# Sheet1_Pt100.net
KiCad netlist of a schematic drawn in Altium Designer
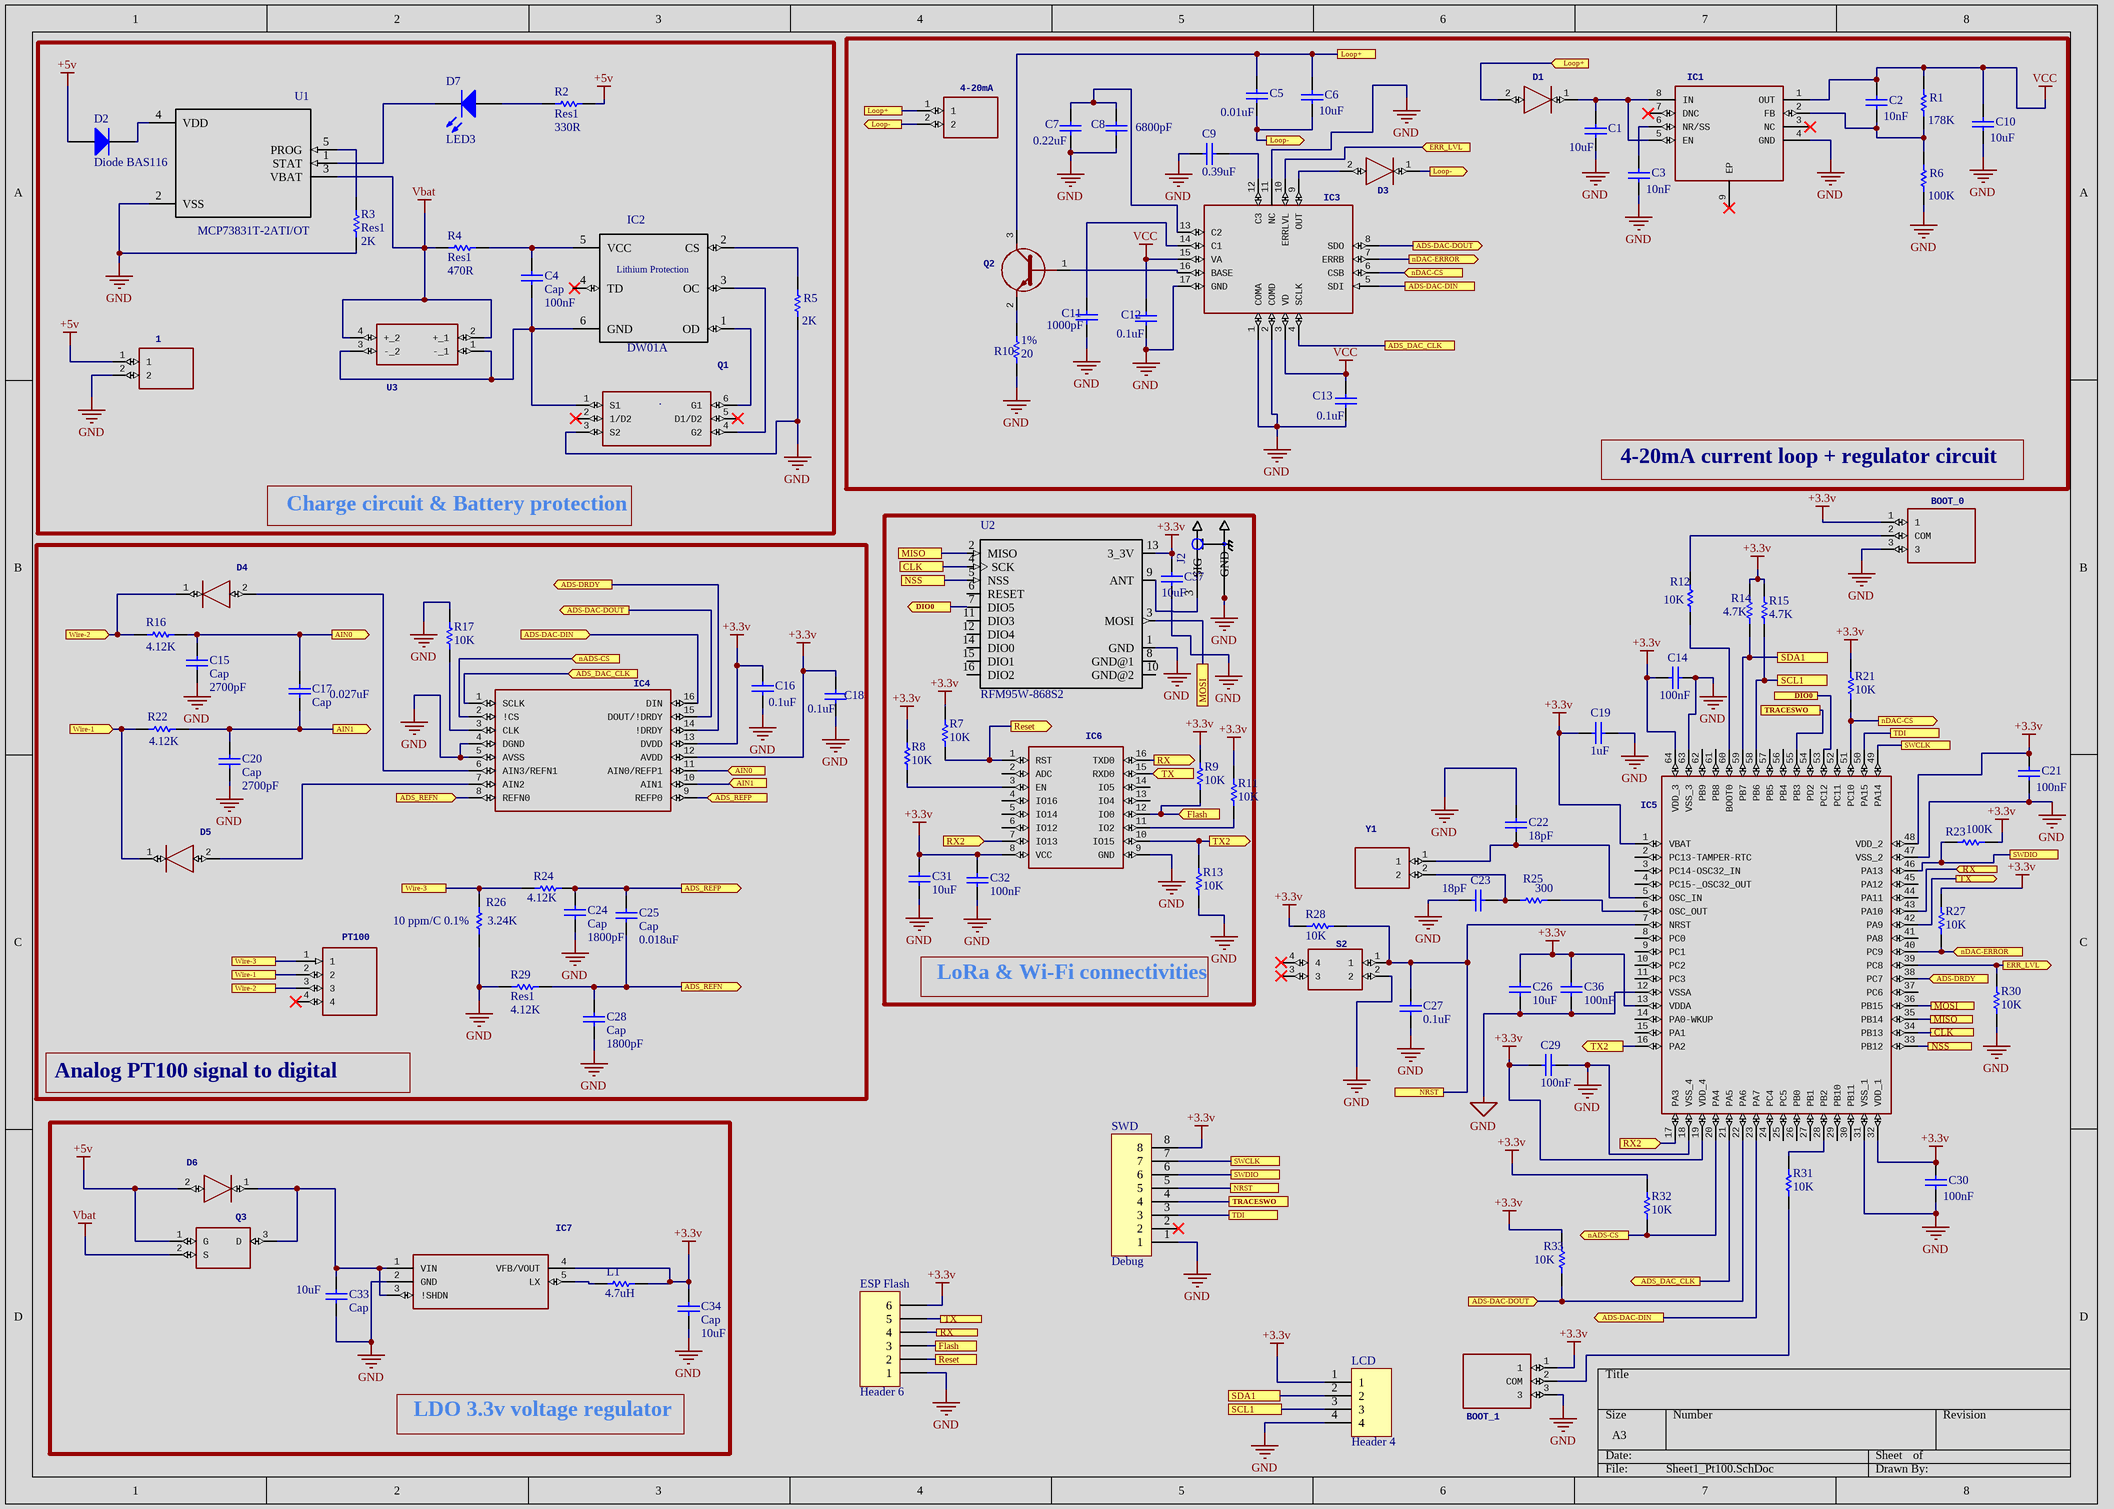
[diagram p0: Sheet1_Pt100.SchDoc]

(export (version "E")
  (design (tool "Eeschema 10.0.6"))
  (components
    (comp (ref "1")
      (value "P=3.81mm Screw terminal   Source:  Datasheet")
      (footprint "SHDR2W80P0X381_1X2_802X740X880")
      (fields (field (name "MANUFACTURER_PART_NUMBER") "DB125-3.81-2P"))
      (libsource (lib "DB125-3") (part "DB125-3.81-2P"))
    )
    (comp (ref "4-20mA")
      (value "P=3.81mm Screw terminal   Source:  Datasheet")
      (footprint "SHDR2W80P0X381_1X2_802X740X880")
      (fields (field (name "MANUFACTURER_PART_NUMBER") "DB125-3.81-2P"))
      (libsource (lib "DB125-3") (part "DB125-3.81-2P"))
    )
    (comp (ref "BOOT_0")
      (value "Slide Switch   Source:  Datasheet")
      (footprint "3PIN_SLIDE_SWITCH")
      (fields
        (field (name "MANUFACTURER_PART_NUMBER") "EG1218")
        (field (name "MOUSER_PART_NUMBER") "612-EG1218")
      )
      (libsource (lib "EG1218") (part "EG1218"))
    )
    (comp (ref "BOOT_1")
      (value "Slide Switch   Source:  Datasheet")
      (footprint "3PIN_SLIDE_SWITCH")
      (fields
        (field (name "MANUFACTURER_PART_NUMBER") "EG1218")
        (field (name "MOUSER_PART_NUMBER") "612-EG1218")
      )
      (libsource (lib "EG1218") (part "EG1218"))
    )
    (comp (ref "C1")
      (value "10uF")
      (footprint "C1206")
      (description "Capacitor")
      (fields (field (name "PUBLISHER") "Altium Limited"))
      (libsource (lib "Miscellaneous Devices") (part "Cap"))
    )
    (comp (ref "C2")
      (value "10nF")
      (footprint "C1206")
      (description "Capacitor")
      (fields (field (name "PUBLISHER") "Altium Limited"))
      (libsource (lib "Miscellaneous Devices") (part "Cap"))
    )
    (comp (ref "C3")
      (value "10nF")
      (footprint "C1206")
      (description "Capacitor")
      (fields (field (name "PUBLISHER") "Altium Limited"))
      (libsource (lib "Miscellaneous Devices") (part "Cap"))
    )
    (comp (ref "C4")
      (value "Cap")
      (footprint "C1206")
      (description "Capacitor")
      (fields (field (name "ALTIUM_VALUE") "100nF") (field (name "PUBLISHER") "Altium Limited"))
      (libsource (lib "Miscellaneous Devices") (part "Cap"))
    )
    (comp (ref "C5")
      (value "0.01uF")
      (footprint "C1206")
      (description "Capacitor")
      (fields (field (name "PUBLISHER") "Altium Limited"))
      (libsource (lib "Miscellaneous Devices") (part "Cap"))
    )
    (comp (ref "C6")
      (value "10uF")
      (footprint "C1206")
      (description "Capacitor")
      (fields (field (name "PUBLISHER") "Altium Limited"))
      (libsource (lib "Miscellaneous Devices") (part "Cap"))
    )
    (comp (ref "C7")
      (value "0.22uF")
      (footprint "C1206")
      (description "Capacitor")
      (fields (field (name "PUBLISHER") "Altium Limited"))
      (libsource (lib "Miscellaneous Devices") (part "Cap"))
    )
    (comp (ref "C8")
      (value "6800pF")
      (footprint "C1206")
      (description "Capacitor")
      (fields (field (name "PUBLISHER") "Altium Limited"))
      (libsource (lib "Miscellaneous Devices") (part "Cap"))
    )
    (comp (ref "C9")
      (value "0.39uF")
      (footprint "C1206")
      (description "Capacitor")
      (fields (field (name "PUBLISHER") "Altium Limited"))
      (libsource (lib "Miscellaneous Devices") (part "Cap"))
    )
    (comp (ref "C10")
      (value "10uF")
      (footprint "C1206")
      (description "Capacitor")
      (fields (field (name "PUBLISHER") "Altium Limited"))
      (libsource (lib "Miscellaneous Devices") (part "Cap"))
    )
    (comp (ref "C11")
      (value "1000pF")
      (footprint "C1206")
      (description "Capacitor")
      (fields (field (name "PUBLISHER") "Altium Limited"))
      (libsource (lib "Miscellaneous Devices") (part "Cap"))
    )
    (comp (ref "C12")
      (value "0.1uF")
      (footprint "C1206")
      (description "Capacitor")
      (fields (field (name "PUBLISHER") "Altium Limited"))
      (libsource (lib "Miscellaneous Devices") (part "Cap"))
    )
    (comp (ref "C13")
      (value "0.1uF")
      (footprint "C1206")
      (description "Capacitor")
      (fields (field (name "PUBLISHER") "Altium Limited"))
      (libsource (lib "Miscellaneous Devices") (part "Cap"))
    )
    (comp (ref "C14")
      (value "100nF")
      (footprint "C1206")
      (description "Capacitor")
      (fields (field (name "PUBLISHER") "Altium Limited"))
      (libsource (lib "Miscellaneous Devices") (part "Cap"))
    )
    (comp (ref "C15")
      (value "Cap")
      (footprint "C1206")
      (description "Capacitor")
      (fields (field (name "ALTIUM_VALUE") "2700pF") (field (name "PUBLISHER") "Altium Limited"))
      (libsource (lib "Miscellaneous Devices") (part "Cap"))
    )
    (comp (ref "C16")
      (value "0.1uF")
      (footprint "C1206")
      (description "Capacitor")
      (fields (field (name "PUBLISHER") "Altium Limited"))
      (libsource (lib "Miscellaneous Devices") (part "Cap"))
    )
    (comp (ref "C17")
      (value "Cap")
      (footprint "C1206")
      (description "Capacitor")
      (fields (field (name "ALTIUM_VALUE") "0.027uF") (field (name "PUBLISHER") "Altium Limited"))
      (libsource (lib "Miscellaneous Devices") (part "Cap"))
    )
    (comp (ref "C18")
      (value "0.1uF")
      (footprint "C1206")
      (description "Capacitor")
      (fields (field (name "PUBLISHER") "Altium Limited"))
      (libsource (lib "Miscellaneous Devices") (part "Cap"))
    )
    (comp (ref "C19")
      (value "1uF")
      (footprint "C1206")
      (description "Capacitor")
      (fields (field (name "PUBLISHER") "Altium Limited"))
      (libsource (lib "Miscellaneous Devices") (part "Cap"))
    )
    (comp (ref "C20")
      (value "Cap")
      (footprint "C1206")
      (description "Capacitor")
      (fields (field (name "ALTIUM_VALUE") "2700pF") (field (name "PUBLISHER") "Altium Limited"))
      (libsource (lib "Miscellaneous Devices") (part "Cap"))
    )
    (comp (ref "C21")
      (value "100nF")
      (footprint "C1206")
      (description "Capacitor")
      (fields (field (name "PUBLISHER") "Altium Limited"))
      (libsource (lib "Miscellaneous Devices") (part "Cap"))
    )
    (comp (ref "C22")
      (value "18pF")
      (footprint "C1206")
      (description "Capacitor")
      (fields (field (name "PUBLISHER") "Altium Limited"))
      (libsource (lib "Miscellaneous Devices") (part "Cap"))
    )
    (comp (ref "C23")
      (value "18pF")
      (footprint "C1206")
      (description "Capacitor")
      (fields (field (name "PUBLISHER") "Altium Limited"))
      (libsource (lib "Miscellaneous Devices") (part "Cap"))
    )
    (comp (ref "C24")
      (value "Cap")
      (footprint "C1206")
      (description "Capacitor")
      (fields (field (name "ALTIUM_VALUE") "1800pF") (field (name "PUBLISHER") "Altium Limited"))
      (libsource (lib "Miscellaneous Devices") (part "Cap"))
    )
    (comp (ref "C25")
      (value "Cap")
      (footprint "C1206")
      (description "Capacitor")
      (fields (field (name "ALTIUM_VALUE") "0.018uF") (field (name "PUBLISHER") "Altium Limited"))
      (libsource (lib "Miscellaneous Devices") (part "Cap"))
    )
    (comp (ref "C26")
      (value "10uF")
      (footprint "C1206")
      (description "Capacitor")
      (fields (field (name "PUBLISHER") "Altium Limited"))
      (libsource (lib "Miscellaneous Devices") (part "Cap"))
    )
    (comp (ref "C27")
      (value "0.1uF")
      (footprint "C1206")
      (description "Capacitor")
      (fields (field (name "PUBLISHER") "Altium Limited"))
      (libsource (lib "Miscellaneous Devices") (part "Cap"))
    )
    (comp (ref "C28")
      (value "Cap")
      (footprint "C1206")
      (description "Capacitor")
      (fields (field (name "ALTIUM_VALUE") "1800pF") (field (name "PUBLISHER") "Altium Limited"))
      (libsource (lib "Miscellaneous Devices") (part "Cap"))
    )
    (comp (ref "C29")
      (value "100nF")
      (footprint "C1206")
      (description "Capacitor")
      (fields (field (name "PUBLISHER") "Altium Limited"))
      (libsource (lib "Miscellaneous Devices") (part "Cap"))
    )
    (comp (ref "C30")
      (value "100nF")
      (footprint "C1206")
      (description "Capacitor")
      (fields (field (name "PUBLISHER") "Altium Limited"))
      (libsource (lib "Miscellaneous Devices") (part "Cap"))
    )
    (comp (ref "C31")
      (value "10uF")
      (footprint "C1206")
      (description "Capacitor")
      (fields (field (name "PUBLISHER") "Altium Limited"))
      (libsource (lib "Miscellaneous Devices") (part "Cap"))
    )
    (comp (ref "C32")
      (value "100nF")
      (footprint "C1206")
      (description "Capacitor")
      (fields (field (name "PUBLISHER") "Altium Limited"))
      (libsource (lib "Miscellaneous Devices") (part "Cap"))
    )
    (comp (ref "C33")
      (value "Cap")
      (footprint "C1206")
      (description "Capacitor")
      (fields (field (name "ALTIUM_VALUE") "10uF") (field (name "PUBLISHER") "Altium Limited"))
      (libsource (lib "Miscellaneous Devices") (part "Cap"))
    )
    (comp (ref "C34")
      (value "Cap")
      (footprint "C1206")
      (description "Capacitor")
      (fields (field (name "ALTIUM_VALUE") "10uF") (field (name "PUBLISHER") "Altium Limited"))
      (libsource (lib "Miscellaneous Devices") (part "Cap"))
    )
    (comp (ref "C36")
      (value "100nF")
      (footprint "C1206")
      (description "Capacitor")
      (fields (field (name "PUBLISHER") "Altium Limited"))
      (libsource (lib "Miscellaneous Devices") (part "Cap"))
    )
    (comp (ref "C37")
      (value "10uF")
      (footprint "C1206")
      (description "Capacitor")
      (fields (field (name "PUBLISHER") "Altium Limited"))
      (libsource (lib "Miscellaneous Devices") (part "Cap"))
    )
    (comp (ref "D1")
      (value "Diodes Inc 40V 350mA, Diode, 2-Pin SOD-523 ZHCS350TA   Source:  Datasheet")
      (footprint "SODFL1608X65N")
      (fields
        (field (name "MANUFACTURER_PART_NUMBER") "ZHCS350TA")
        (field (name "MOUSER_PART_NUMBER") "522-ZHCS350TA")
        (field (name "RS_PART_NUMBER") "7515168P")
      )
      (libsource (lib "ZHCS350TA") (part "ZHCS350TA"))
    )
    (comp (ref "D2")
      (value "Diode BAS116")
      (footprint "SOT-23_N")
      (description "Silicon Low Leakage Diode")
      (fields (field (name "PUBLISHER") "Altium Limited"))
      (libsource (lib "Miscellaneous Devices") (part "Diode BAS116"))
    )
    (comp (ref "D3")
      (value "Diodes Inc 40V 350mA, Diode, 2-Pin SOD-523 ZHCS350TA   Source:  Datasheet")
      (footprint "SODFL1608X65N")
      (fields
        (field (name "MANUFACTURER_PART_NUMBER") "ZHCS350TA")
        (field (name "MOUSER_PART_NUMBER") "522-ZHCS350TA")
        (field (name "RS_PART_NUMBER") "7515168P")
      )
      (libsource (lib "ZHCS350TA") (part "ZHCS350TA"))
    )
    (comp (ref "D4")
      (value "Diodes Inc 40V 350mA, Diode, 2-Pin SOD-523 ZHCS350TA   Source:  Datasheet")
      (footprint "SODFL1608X65N")
      (fields
        (field (name "MANUFACTURER_PART_NUMBER") "ZHCS350TA")
        (field (name "MOUSER_PART_NUMBER") "522-ZHCS350TA")
        (field (name "RS_PART_NUMBER") "7515168P")
      )
      (libsource (lib "ZHCS350TA") (part "ZHCS350TA"))
    )
    (comp (ref "D5")
      (value "Diodes Inc 40V 350mA, Diode, 2-Pin SOD-523 ZHCS350TA   Source:  Datasheet")
      (footprint "SODFL1608X65N")
      (fields
        (field (name "MANUFACTURER_PART_NUMBER") "ZHCS350TA")
        (field (name "MOUSER_PART_NUMBER") "522-ZHCS350TA")
        (field (name "RS_PART_NUMBER") "7515168P")
      )
      (libsource (lib "ZHCS350TA") (part "ZHCS350TA"))
    )
    (comp (ref "D6")
      (value "Diode, NXP, PMEG3010ER NXP PMEG3010ER, SMT Schottky Diode, 30V 1A, 2-Pin SOD-123   Source:  Datasheet")
      (footprint "SODFL3517X110N")
      (fields (field (name "MANUFACTURER_PART_NUMBER") "PMEG3010ER"))
      (libsource (lib "PMEG3010ER") (part "PMEG3010ER"))
    )
    (comp (ref "D7")
      (value "LED3")
      (footprint "3.5X2.8X1.9")
      (description "Typical BLUE SiC LED")
      (fields (field (name "PUBLISHER") "Altium Limited"))
      (libsource (lib "Miscellaneous Devices") (part "LED3"))
    )
    (comp (ref "ESP Flash")
      (value "Header 6")
      (footprint "HDR1X6")
      (description "Header, 6-Pin")
      (fields (field (name "PUBLISHER") "Altium Limited"))
      (libsource (lib "Miscellaneous Connectors") (part "Header 6"))
    )
    (comp (ref "IC1")
      (value "Vin 3V to 36V, 150mA, Ultra-Low-Noise, High-PSRR Low-Dropout (LDO) Linear Regulator   Source:  Datasheet")
      (footprint "SOP65P490X110-9N")
      (fields
        (field (name "MANUFACTURER_PART_NUMBER") "TPS7A4901DGNR")
        (field (name "MOUSER_PART_NUMBER") "595-TPS7A4901DGNR")
      )
      (libsource (lib "TPS7A4901DGNR") (part "TPS7A4901DGNR"))
    )
    (comp (ref "IC2")
      (value "DW01A")
      (footprint "*SOT23-6")
      (description "One Cell Lithium-ion/Polymer Battery Protection IC")
      (fields (field (name "MF") "Fortune Semiconductor"))
      (libsource (lib "DW01A") (part "DW01A"))
    )
    (comp (ref "IC3")
      (value "16-Bit Precision DAC With Internal Reference and 4mA-to-20mA Current Loop Drive   Source:  Datasheet")
      (footprint "QFN50P400X400X80-17N")
      (fields
        (field (name "MANUFACTURER_PART_NUMBER") "DAC161S997RGHR")
        (field (name "MOUSER_PART_NUMBER") "595-DAC161S997RGHR")
      )
      (libsource (lib "DAC161S997RGHR") (part "DAC161S997RGHR"))
    )
    (comp (ref "IC4")
      (value "24-bit, 2-kSPS, 4-ch, low-power, small-size delta-sigma ADC w/ PGA, VREF, 2x IDACs & SPI interface   Source:  Datasheet")
      (footprint "SOP65P640X120-16N")
      (fields
        (field (name "MANUFACTURER_PART_NUMBER") "ADS1220IPWR")
        (field (name "MOUSER_PART_NUMBER") "595-ADS1220IPWR")
      )
      (libsource (lib "ADS1220IPWR") (part "ADS1220IPWR"))
    )
    (comp (ref "IC5")
      (value "STM32F103RBT6, 32 bit ARM Cortex M3 Microcontroller 72MHz 128kb Flash, 20kb RAM, USB I2C SPI 64-Pin LQFP   Source:  Datasheet")
      (footprint "STM32F103RBT6:*QFP50P1200X1200X160-64N")
      (fields
        (field (name "MANUFACTURER_PART_NUMBER") "STM32F103RBT6")
        (field (name "MOUSER_PART_NUMBER") "511-STM32F103RBT6")
        (field (name "RS_PART_NUMBER") "0402251P")
      )
      (libsource (lib "STM32F103RBT6") (part "STM32F103RBT6"))
    )
    (comp (ref "IC6")
      (value "RF SOLUTIONS - ESP-12S - WIFI MODULE, 2.484GHZ, 9 I/O PORT   Source:  Datasheet")
      (footprint "ESP12S")
      (fields
        (field (name "MANUFACTURER_PART_NUMBER") "ESP-12S")
        (field (name "MOUSER_PART_NUMBER") "223-ESP-12S")
        (field (name "RS_PART_NUMBER") "1697593")
      )
      (libsource (lib "ESP-12S") (part "ESP-12S"))
    )
    (comp (ref "IC7")
      (value "Sw. Reg. PWM/PFM 2MHz 500mA 3.3V TSOT5   Source:  Datasheet")
      (footprint "SOT95P280X110-5N")
      (fields
        (field (name "MANUFACTURER_PART_NUMBER") "MCP1603T-330I/OS")
        (field (name "MOUSER_PART_NUMBER") "579-MCP1603T-330I/OS")
        (field (name "RS_PART_NUMBER") "7386235P")
      )
      (libsource (lib "MCP1603T-330I_OS") (part "MCP1603T-330I_OS"))
    )
    (comp (ref "J2")
      (value "U.FL-R-SMT(01)")
      (footprint "*HRS_U.FL-R-SMT(01)")
      (description "U.FL _UMCC_ Connector Receptacle, Male Pin 50Ohm Surface Mount Solder")
      (fields (field (name "MF") "Hirose") (field (name "MP") "U.FL-R-SMT_01_"))
      (libsource (lib "U.FL-R-SMT_01_") (part "U.FL-R-SMT(01)"))
    )
    (comp (ref "L1")
      (value "4.7uH")
      (footprint "Miscellaneous Devices:C1206")
      (description "Resistor")
      (fields (field (name "PUBLISHER") "Altium Limited"))
      (libsource (lib "Miscellaneous Devices") (part "Res1"))
    )
    (comp (ref "LCD")
      (value "Header 4")
      (footprint "HDR1X4")
      (description "Header, 4-Pin")
      (fields (field (name "PUBLISHER") "Altium Limited"))
      (libsource (lib "Miscellaneous Connectors") (part "Header 4"))
    )
    (comp (ref "PT100")
      (value "European P.C.B. type terminal blocks  EK series 4 pole   Source:  Datasheet")
      (footprint "SHDR4W90P0X381_1X4_1524X740X85")
      (fields (field (name "MANUFACTURER_PART_NUMBER") "EK381V-04P"))
      (libsource (lib "EK381V-04P") (part "EK381V-04P"))
    )
    (comp (ref "Q1")
      (value "Dual N-Channel Enhancement Mode MOSFET   Source:  Datasheet")
      (footprint "UMW8205A:SOT95P285X140-6N")
      (fields (field (name "MANUFACTURER_PART_NUMBER") "UMW8205A"))
      (libsource (lib "UMW8205A") (part "UMW8205A"))
    )
    (comp (ref "Q2")
      (value "MMBT3904 - NPN switching transistor   Source:  Datasheet")
      (footprint "SOT95P230X110-3N")
      (fields
        (field (name "MANUFACTURER_PART_NUMBER") "MMBT3904VL")
        (field (name "MOUSER_PART_NUMBER") "771-MMBT3904VL")
      )
      (libsource (lib "MMBT3904VL") (part "MMBT3904VL"))
    )
    (comp (ref "Q3")
      (value "INFINEON - IRLML6401TRPBF - MOSFET, P, MICRO3   Source:  Datasheet")
      (footprint "SOT95P237X112-3N")
      (fields
        (field (name "MANUFACTURER_PART_NUMBER") "IRLML6401TRPBF")
        (field (name "MOUSER_PART_NUMBER") "942-IRLML6401TRPBF")
        (field (name "RS_PART_NUMBER") "0301316P")
      )
      (libsource (lib "IRLML6401TRPBF") (part "IRLML6401TRPBF"))
    )
    (comp (ref "R1")
      (value "178K")
      (footprint "Miscellaneous Devices:C1206")
      (description "Resistor")
      (fields (field (name "PUBLISHER") "Altium Limited"))
      (libsource (lib "Miscellaneous Devices") (part "Res1"))
    )
    (comp (ref "R2")
      (value "Res1")
      (footprint "Miscellaneous Devices:C1206")
      (description "Resistor")
      (fields (field (name "ALTIUM_VALUE") "330R") (field (name "PUBLISHER") "Altium Limited"))
      (libsource (lib "Miscellaneous Devices") (part "Res1"))
    )
    (comp (ref "R3")
      (value "Res1")
      (footprint "Miscellaneous Devices:C1206")
      (description "Resistor")
      (fields (field (name "ALTIUM_VALUE") "2K") (field (name "PUBLISHER") "Altium Limited"))
      (libsource (lib "Miscellaneous Devices") (part "Res1"))
    )
    (comp (ref "R4")
      (value "Res1")
      (footprint "Miscellaneous Devices:C1206")
      (description "Resistor")
      (fields (field (name "ALTIUM_VALUE") "470R") (field (name "PUBLISHER") "Altium Limited"))
      (libsource (lib "Miscellaneous Devices") (part "Res1"))
    )
    (comp (ref "R5")
      (value "2K")
      (footprint "Miscellaneous Devices:C1206")
      (description "Resistor")
      (fields (field (name "PUBLISHER") "Altium Limited"))
      (libsource (lib "Miscellaneous Devices") (part "Res1"))
    )
    (comp (ref "R6")
      (value "100K")
      (footprint "Miscellaneous Devices:C1206")
      (description "Resistor")
      (fields (field (name "PUBLISHER") "Altium Limited"))
      (libsource (lib "Miscellaneous Devices") (part "Res1"))
    )
    (comp (ref "R7")
      (value "10K")
      (footprint "Miscellaneous Devices:C1206")
      (description "Resistor")
      (fields (field (name "PUBLISHER") "Altium Limited"))
      (libsource (lib "Miscellaneous Devices") (part "Res1"))
    )
    (comp (ref "R8")
      (value "10K")
      (footprint "Miscellaneous Devices:C1206")
      (description "Resistor")
      (fields (field (name "PUBLISHER") "Altium Limited"))
      (libsource (lib "Miscellaneous Devices") (part "Res1"))
    )
    (comp (ref "R9")
      (value "10K")
      (footprint "Miscellaneous Devices:C1206")
      (description "Resistor")
      (fields (field (name "PUBLISHER") "Altium Limited"))
      (libsource (lib "Miscellaneous Devices") (part "Res1"))
    )
    (comp (ref "R10")
      (value "1%")
      (footprint "Miscellaneous Devices:C1206")
      (description "Resistor")
      (fields (field (name "ALTIUM_VALUE") "20") (field (name "PUBLISHER") "Altium Limited"))
      (libsource (lib "Miscellaneous Devices") (part "Res1"))
    )
    (comp (ref "R11")
      (value "10K")
      (footprint "Miscellaneous Devices:C1206")
      (description "Resistor")
      (fields (field (name "PUBLISHER") "Altium Limited"))
      (libsource (lib "Miscellaneous Devices") (part "Res1"))
    )
    (comp (ref "R12")
      (value "10K")
      (footprint "Miscellaneous Devices:C1206")
      (description "Resistor")
      (fields (field (name "PUBLISHER") "Altium Limited"))
      (libsource (lib "Miscellaneous Devices") (part "Res1"))
    )
    (comp (ref "R13")
      (value "10K")
      (footprint "Miscellaneous Devices:C1206")
      (description "Resistor")
      (fields (field (name "PUBLISHER") "Altium Limited"))
      (libsource (lib "Miscellaneous Devices") (part "Res1"))
    )
    (comp (ref "R14")
      (value "4.7K")
      (footprint "Miscellaneous Devices:C1206")
      (description "Resistor")
      (fields (field (name "PUBLISHER") "Altium Limited"))
      (libsource (lib "Miscellaneous Devices") (part "Res1"))
    )
    (comp (ref "R15")
      (value "4.7K")
      (footprint "Miscellaneous Devices:C1206")
      (description "Resistor")
      (fields (field (name "PUBLISHER") "Altium Limited"))
      (libsource (lib "Miscellaneous Devices") (part "Res1"))
    )
    (comp (ref "R16")
      (value "4.12K")
      (footprint "Miscellaneous Devices:C1206")
      (description "Resistor")
      (fields (field (name "PUBLISHER") "Altium Limited"))
      (libsource (lib "Miscellaneous Devices") (part "Res1"))
    )
    (comp (ref "R17")
      (value "10K")
      (footprint "Miscellaneous Devices:C1206")
      (description "Resistor")
      (fields (field (name "PUBLISHER") "Altium Limited"))
      (libsource (lib "Miscellaneous Devices") (part "Res1"))
    )
    (comp (ref "R21")
      (value "10K")
      (footprint "Miscellaneous Devices:C1206")
      (description "Resistor")
      (fields (field (name "PUBLISHER") "Altium Limited"))
      (libsource (lib "Miscellaneous Devices") (part "Res1"))
    )
    (comp (ref "R22")
      (value "4.12K")
      (footprint "Miscellaneous Devices:C1206")
      (description "Resistor")
      (fields (field (name "PUBLISHER") "Altium Limited"))
      (libsource (lib "Miscellaneous Devices") (part "Res1"))
    )
    (comp (ref "R23")
      (value "100K")
      (footprint "Miscellaneous Devices:C1206")
      (description "Resistor")
      (fields (field (name "PUBLISHER") "Altium Limited"))
      (libsource (lib "Miscellaneous Devices") (part "Res1"))
    )
    (comp (ref "R24")
      (value "4.12K")
      (footprint "Miscellaneous Devices:C1206")
      (description "Resistor")
      (fields (field (name "PUBLISHER") "Altium Limited"))
      (libsource (lib "Miscellaneous Devices") (part "Res1"))
    )
    (comp (ref "R25")
      (value "300")
      (footprint "Miscellaneous Devices:C1206")
      (description "Resistor")
      (fields (field (name "PUBLISHER") "Altium Limited"))
      (libsource (lib "Miscellaneous Devices") (part "Res1"))
    )
    (comp (ref "R26")
      (value "10 ppm/C 0.1%")
      (footprint "Miscellaneous Devices:C1206")
      (description "Resistor")
      (fields (field (name "ALTIUM_VALUE") "3.24K") (field (name "PUBLISHER") "Altium Limited"))
      (libsource (lib "Miscellaneous Devices") (part "Res1"))
    )
    (comp (ref "R27")
      (value "10K")
      (footprint "Miscellaneous Devices:C1206")
      (description "Resistor")
      (fields (field (name "PUBLISHER") "Altium Limited"))
      (libsource (lib "Miscellaneous Devices") (part "Res1"))
    )
    (comp (ref "R28")
      (value "10K")
      (footprint "Miscellaneous Devices:C1206")
      (description "Resistor")
      (fields (field (name "PUBLISHER") "Altium Limited"))
      (libsource (lib "Miscellaneous Devices") (part "Res1"))
    )
    (comp (ref "R29")
      (value "Res1")
      (footprint "Miscellaneous Devices:C1206")
      (description "Resistor")
      (fields (field (name "ALTIUM_VALUE") "4.12K") (field (name "PUBLISHER") "Altium Limited"))
      (libsource (lib "Miscellaneous Devices") (part "Res1"))
    )
    (comp (ref "R30")
      (value "10K")
      (footprint "Miscellaneous Devices:C1206")
      (description "Resistor")
      (fields (field (name "PUBLISHER") "Altium Limited"))
      (libsource (lib "Miscellaneous Devices") (part "Res1"))
    )
    (comp (ref "R31")
      (value "10K")
      (footprint "Miscellaneous Devices:C1206")
      (description "Resistor")
      (fields (field (name "PUBLISHER") "Altium Limited"))
      (libsource (lib "Miscellaneous Devices") (part "Res1"))
    )
    (comp (ref "R32")
      (value "10K")
      (footprint "Miscellaneous Devices:C1206")
      (description "Resistor")
      (fields (field (name "PUBLISHER") "Altium Limited"))
      (libsource (lib "Miscellaneous Devices") (part "Res1"))
    )
    (comp (ref "R33")
      (value "10K")
      (footprint "Miscellaneous Devices:C1206")
      (description "Resistor")
      (fields (field (name "PUBLISHER") "Altium Limited"))
      (libsource (lib "Miscellaneous Devices") (part "Res1"))
    )
    (comp (ref "S2")
      (value "IP67 Button Tactile Switch, SPST 50 mA 3.5mm Surface Mount   Source:  Datasheet")
      (footprint "KSC401G50SHLFS")
      (fields
        (field (name "MANUFACTURER_PART_NUMBER") "KSC222GLFS")
        (field (name "MOUSER_PART_NUMBER") "611-KSC222GLFS")
        (field (name "RS_PART_NUMBER") "8998582")
      )
      (libsource (lib "KSC222GLFS") (part "KSC222GLFS"))
    )
    (comp (ref "SWD")
      (value "Debug")
      (footprint "HDR1X8")
      (description "Header, 8-Pin")
      (fields (field (name "PUBLISHER") "Altium Limited"))
      (libsource (lib "Miscellaneous Connectors") (part "Header 8"))
    )
    (comp (ref "U1")
      (value "MCP73831T-2ATI/OT")
      (footprint "MCP73831T-2ATI_OT:*SOT95P280X145-5N")
      (description "MCP73831 Series Li-Ion/Li-Pol 15 mA - 500 mA 4.2 V Charge Controller - SOT-23-5")
      (fields (field (name "MF") "Microchip"))
      (libsource (lib "Miscellaneous Devices") (part "MCP73831T-2ATI/OT"))
    )
    (comp (ref "U2")
      (value "RFM95W-868S2")
      (footprint "*XCVR_RFM95W-868S2")
      (description "RFM95W 869/915MHZ RF Transceiver Module")
      (fields (field (name "MF") "RF"))
      (libsource (lib "RFM95W-868S2") (part "RFM95W-868S2"))
    )
    (comp (ref "U3")
      (value "KEYSTONE - 1048 - BATTERY HOLDER, 18650 LI-ION, 2CELL, SMD   Source:  Datasheet")
      (footprint "1048")
      (fields (field (name "MANUFACTURER_PART_NUMBER") "1048") (field (name "MOUSER_PART_NUMBER") "534-1048"))
      (libsource (lib "1048") (part "1048"))
    )
    (comp (ref "Y1")
      (value "Automotive use crystal unit, 2-pin, NX5032GA   Source:  Datasheet")
      (footprint "NX5032GA")
      (fields
        (field (name "MANUFACTURER_PART_NUMBER") "NX5032GA-8.000M-STD-CSU-1")
        (field (name "MOUSER_PART_NUMBER") "344-NX5032GA8MCSU1")
        (field (name "RS_PART_NUMBER") "1847981")
      )
      (libsource (lib "NX5032GA-8") (part "NX5032GA-8.000M-STD-CSU-1"))
    )
  )
  (nets
    (net (code "1") (name "+3.3v") (class "Default")
      (node (ref "BOOT_0") (pin "1") (pinfunction "1_1") (pintype "bidirectional"))
      (node (ref "BOOT_1") (pin "1") (pinfunction "1_1") (pintype "bidirectional"))
      (node (ref "C14") (pin "2") (pinfunction "2_2") (pintype "passive"))
      (node (ref "C16") (pin "2") (pinfunction "2_2") (pintype "passive"))
      (node (ref "C18") (pin "2") (pinfunction "2_2") (pintype "passive"))
      (node (ref "C19") (pin "1") (pinfunction "1_1") (pintype "passive"))
      (node (ref "C21") (pin "2") (pinfunction "2_2") (pintype "passive"))
      (node (ref "C26") (pin "2") (pinfunction "2_2") (pintype "passive"))
      (node (ref "C29") (pin "2") (pinfunction "2_2") (pintype "passive"))
      (node (ref "C30") (pin "2") (pinfunction "2_2") (pintype "passive"))
      (node (ref "C31") (pin "2") (pinfunction "2_2") (pintype "passive"))
      (node (ref "C32") (pin "2") (pinfunction "2_2") (pintype "passive"))
      (node (ref "C34") (pin "2") (pinfunction "2_2") (pintype "passive"))
      (node (ref "C36") (pin "2") (pinfunction "2_2") (pintype "passive"))
      (node (ref "C37") (pin "2") (pinfunction "2_2") (pintype "passive"))
      (node (ref "ESP Flash") (pin "6") (pinfunction "6_6") (pintype "passive"))
      (node (ref "IC4") (pin "12") (pinfunction "AVDD_12") (pintype "bidirectional"))
      (node (ref "IC4") (pin "13") (pinfunction "DVDD_13") (pintype "bidirectional"))
      (node (ref "IC5") (pin "1") (pinfunction "VBAT_1") (pintype "bidirectional"))
      (node (ref "IC5") (pin "13") (pinfunction "VDDA_13") (pintype "bidirectional"))
      (node (ref "IC5") (pin "19") (pinfunction "VDD_4_19") (pintype "bidirectional"))
      (node (ref "IC5") (pin "32") (pinfunction "VDD_1_32") (pintype "bidirectional"))
      (node (ref "IC5") (pin "48") (pinfunction "VDD_2_48") (pintype "bidirectional"))
      (node (ref "IC5") (pin "64") (pinfunction "VDD_3_64") (pintype "bidirectional"))
      (node (ref "IC6") (pin "8") (pinfunction "VCC_8") (pintype "bidirectional"))
      (node (ref "IC7") (pin "4") (pinfunction "VFB/VOUT_4") (pintype "power_in"))
      (node (ref "L1") (pin "1") (pinfunction "1_1") (pintype "passive"))
      (node (ref "LCD") (pin "1") (pinfunction "1_1") (pintype "power_in"))
      (node (ref "R11") (pin "1") (pinfunction "1_1") (pintype "passive"))
      (node (ref "R14") (pin "2") (pinfunction "2_2") (pintype "passive"))
      (node (ref "R15") (pin "2") (pinfunction "2_2") (pintype "passive"))
      (node (ref "R21") (pin "2") (pinfunction "2_2") (pintype "passive"))
      (node (ref "R23") (pin "1") (pinfunction "1_1") (pintype "passive"))
      (node (ref "R27") (pin "2") (pinfunction "2_2") (pintype "passive"))
      (node (ref "R28") (pin "2") (pinfunction "2_2") (pintype "passive"))
      (node (ref "R32") (pin "2") (pinfunction "2_2") (pintype "passive"))
      (node (ref "R33") (pin "2") (pinfunction "2_2") (pintype "passive"))
      (node (ref "R7") (pin "1") (pinfunction "1_1") (pintype "passive"))
      (node (ref "R8") (pin "1") (pinfunction "1_1") (pintype "passive"))
      (node (ref "R9") (pin "1") (pinfunction "1_1") (pintype "passive"))
      (node (ref "SWD") (pin "8") (pinfunction "8_8") (pintype "power_in"))
      (node (ref "U2") (pin "13") (pinfunction "3_3V_13") (pintype "power_in"))
    )
    (net (code "2") (name "+5v") (class "Default")
      (node (ref "1") (pin "1") (pinfunction "1_1") (pintype "bidirectional"))
      (node (ref "D2") (pin "1") (pinfunction "A_1") (pintype "passive"))
      (node (ref "D6") (pin "2") (pinfunction "A_2") (pintype "bidirectional"))
      (node (ref "Q3") (pin "1") (pinfunction "G_1") (pintype "bidirectional"))
      (node (ref "R2") (pin "1") (pinfunction "1_1") (pintype "passive"))
    )
    (net (code "3") (name "/ADS-DAC-DIN") (class "Default")
      (node (ref "IC3") (pin "5") (pinfunction "SDI_5") (pintype "input"))
      (node (ref "IC4") (pin "16") (pinfunction "DIN_16") (pintype "bidirectional"))
      (node (ref "IC5") (pin "23") (pinfunction "PA7_23") (pintype "bidirectional"))
    )
    (net (code "4") (name "/ADS-DAC-DOUT") (class "Default")
      (node (ref "IC3") (pin "8") (pinfunction "SDO_8") (pintype "bidirectional"))
      (node (ref "IC4") (pin "15") (pinfunction "DOUT/!DRDY_15") (pintype "bidirectional"))
      (node (ref "IC5") (pin "22") (pinfunction "PA6_22") (pintype "bidirectional"))
      (node (ref "R33") (pin "1") (pinfunction "1_1") (pintype "passive"))
    )
    (net (code "5") (name "/ADS-DRDY") (class "Default")
      (node (ref "IC4") (pin "14") (pinfunction "!DRDY_14") (pintype "bidirectional"))
      (node (ref "IC5") (pin "38") (pinfunction "PC7_38") (pintype "bidirectional"))
    )
    (net (code "6") (name "/ADS_DAC_CLK") (class "Default")
      (node (ref "IC3") (pin "4") (pinfunction "SCLK_4") (pintype "bidirectional"))
      (node (ref "IC4") (pin "1") (pinfunction "SCLK_1") (pintype "bidirectional"))
      (node (ref "IC5") (pin "21") (pinfunction "PA5_21") (pintype "bidirectional"))
    )
    (net (code "7") (name "/ADS_REFN") (class "Default")
      (node (ref "C25") (pin "1") (pinfunction "1_1") (pintype "passive"))
      (node (ref "C28") (pin "2") (pinfunction "2_2") (pintype "passive"))
      (node (ref "IC4") (pin "8") (pinfunction "REFN0_8") (pintype "bidirectional"))
      (node (ref "R29") (pin "1") (pinfunction "1_1") (pintype "passive"))
    )
    (net (code "8") (name "/ADS_REFP") (class "Default")
      (node (ref "C24") (pin "2") (pinfunction "2_2") (pintype "passive"))
      (node (ref "C25") (pin "2") (pinfunction "2_2") (pintype "passive"))
      (node (ref "IC4") (pin "9") (pinfunction "REFP0_9") (pintype "bidirectional"))
      (node (ref "R24") (pin "1") (pinfunction "1_1") (pintype "passive"))
    )
    (net (code "9") (name "/AIN0") (class "Default")
      (node (ref "C15") (pin "2") (pinfunction "2_2") (pintype "passive"))
      (node (ref "C17") (pin "2") (pinfunction "2_2") (pintype "passive"))
      (node (ref "IC4") (pin "11") (pinfunction "AIN0/REFP1_11") (pintype "bidirectional"))
      (node (ref "R16") (pin "1") (pinfunction "1_1") (pintype "passive"))
    )
    (net (code "10") (name "/AIN1") (class "Default")
      (node (ref "C17") (pin "1") (pinfunction "1_1") (pintype "passive"))
      (node (ref "C20") (pin "2") (pinfunction "2_2") (pintype "passive"))
      (node (ref "IC4") (pin "10") (pinfunction "AIN1_10") (pintype "bidirectional"))
      (node (ref "R22") (pin "1") (pinfunction "1_1") (pintype "passive"))
    )
    (net (code "11") (name "/CLK") (class "Default")
      (node (ref "IC5") (pin "34") (pinfunction "PB13_34") (pintype "bidirectional"))
      (node (ref "U2") (pin "4") (pinfunction "SCK_4") (pintype "input"))
    )
    (net (code "12") (name "/DIO0") (class "Default")
      (node (ref "IC5") (pin "53") (pinfunction "PC12_53") (pintype "bidirectional"))
      (node (ref "U2") (pin "7") (pinfunction "DIO5_7") (pintype "bidirectional"))
    )
    (net (code "13") (name "/ERR_LVL") (class "Default")
      (node (ref "IC3") (pin "10") (pinfunction "ERRLVL_10") (pintype "bidirectional"))
      (node (ref "IC5") (pin "39") (pinfunction "PC8_39") (pintype "bidirectional"))
      (node (ref "R30") (pin "2") (pinfunction "2_2") (pintype "passive"))
    )
    (net (code "14") (name "/Flash") (class "Default")
      (node (ref "ESP Flash") (pin "3") (pinfunction "3_3") (pintype "passive"))
      (node (ref "IC6") (pin "12") (pinfunction "IO0_12") (pintype "bidirectional"))
      (node (ref "R9") (pin "2") (pinfunction "2_2") (pintype "passive"))
    )
    (net (code "15") (name "/Loop+") (class "Default")
      (node (ref "4-20mA") (pin "1") (pinfunction "1_1") (pintype "bidirectional"))
      (node (ref "C5") (pin "2") (pinfunction "2_2") (pintype "passive"))
      (node (ref "C6") (pin "2") (pinfunction "2_2") (pintype "passive"))
      (node (ref "D1") (pin "2") (pinfunction "A_2") (pintype "bidirectional"))
      (node (ref "Q2") (pin "3") (pinfunction "C_3") (pintype "bidirectional"))
    )
    (net (code "16") (name "/Loop-") (class "Default")
      (node (ref "4-20mA") (pin "2") (pinfunction "2_2") (pintype "bidirectional"))
      (node (ref "C5") (pin "1") (pinfunction "1_1") (pintype "passive"))
      (node (ref "C6") (pin "1") (pinfunction "1_1") (pintype "passive"))
      (node (ref "D3") (pin "1") (pinfunction "K_1") (pintype "bidirectional"))
    )
    (net (code "17") (name "/MISO") (class "Default")
      (node (ref "IC5") (pin "35") (pinfunction "PB14_35") (pintype "bidirectional"))
      (node (ref "U2") (pin "2") (pinfunction "MISO_2") (pintype "input"))
    )
    (net (code "18") (name "/MOSI") (class "Default")
      (node (ref "IC5") (pin "36") (pinfunction "PB15_36") (pintype "bidirectional"))
      (node (ref "U2") (pin "3") (pinfunction "MOSI_3") (pintype "output"))
    )
    (net (code "19") (name "/NRST") (class "Default")
      (node (ref "C27") (pin "2") (pinfunction "2_2") (pintype "passive"))
      (node (ref "IC5") (pin "7") (pinfunction "NRST_7") (pintype "bidirectional"))
      (node (ref "R28") (pin "1") (pinfunction "1_1") (pintype "passive"))
      (node (ref "S2") (pin "1") (pinfunction "1_1") (pintype "bidirectional"))
      (node (ref "SWD") (pin "5") (pinfunction "5_5") (pintype "passive"))
    )
    (net (code "20") (name "/NSS") (class "Default")
      (node (ref "IC5") (pin "33") (pinfunction "PB12_33") (pintype "bidirectional"))
      (node (ref "U2") (pin "5") (pinfunction "NSS_5") (pintype "input"))
    )
    (net (code "21") (name "/RX") (class "Default")
      (node (ref "ESP Flash") (pin "4") (pinfunction "4_4") (pintype "passive"))
      (node (ref "IC5") (pin "43") (pinfunction "PA10_43") (pintype "bidirectional"))
      (node (ref "IC6") (pin "16") (pinfunction "TXD0_16") (pintype "bidirectional"))
    )
    (net (code "22") (name "/RX2") (class "Default")
      (node (ref "IC5") (pin "17") (pinfunction "PA3_17") (pintype "bidirectional"))
      (node (ref "IC6") (pin "7") (pinfunction "IO13_7") (pintype "bidirectional"))
    )
    (net (code "23") (name "/Reset") (class "Default")
      (node (ref "ESP Flash") (pin "2") (pinfunction "2_2") (pintype "passive"))
      (node (ref "IC6") (pin "1") (pinfunction "RST_1") (pintype "bidirectional"))
      (node (ref "R7") (pin "2") (pinfunction "2_2") (pintype "passive"))
    )
    (net (code "24") (name "/SCL1") (class "Default")
      (node (ref "IC5") (pin "58") (pinfunction "PB6_58") (pintype "bidirectional"))
      (node (ref "LCD") (pin "3") (pinfunction "3_3") (pintype "passive"))
      (node (ref "R15") (pin "1") (pinfunction "1_1") (pintype "passive"))
    )
    (net (code "25") (name "/SDA1") (class "Default")
      (node (ref "IC5") (pin "59") (pinfunction "PB7_59") (pintype "bidirectional"))
      (node (ref "LCD") (pin "2") (pinfunction "2_2") (pintype "passive"))
      (node (ref "R14") (pin "1") (pinfunction "1_1") (pintype "passive"))
    )
    (net (code "26") (name "/SWCLK") (class "Default")
      (node (ref "IC5") (pin "49") (pinfunction "PA14_49") (pintype "bidirectional"))
      (node (ref "SWD") (pin "7") (pinfunction "7_7") (pintype "passive"))
    )
    (net (code "27") (name "/SWDIO") (class "Default")
      (node (ref "IC5") (pin "46") (pinfunction "PA13_46") (pintype "bidirectional"))
      (node (ref "R23") (pin "2") (pinfunction "2_2") (pintype "passive"))
      (node (ref "SWD") (pin "6") (pinfunction "6_6") (pintype "passive"))
    )
    (net (code "28") (name "/TDI") (class "Default")
      (node (ref "IC5") (pin "50") (pinfunction "PA15_50") (pintype "bidirectional"))
      (node (ref "SWD") (pin "3") (pinfunction "3_3") (pintype "passive"))
    )
    (net (code "29") (name "/TRACESWO") (class "Default")
      (node (ref "IC5") (pin "55") (pinfunction "PB3_55") (pintype "bidirectional"))
      (node (ref "SWD") (pin "4") (pinfunction "4_4") (pintype "passive"))
    )
    (net (code "30") (name "/TX") (class "Default")
      (node (ref "ESP Flash") (pin "5") (pinfunction "5_5") (pintype "passive"))
      (node (ref "IC5") (pin "42") (pinfunction "PA9_42") (pintype "bidirectional"))
      (node (ref "IC6") (pin "15") (pinfunction "RXD0_15") (pintype "bidirectional"))
    )
    (net (code "31") (name "/TX2") (class "Default")
      (node (ref "IC5") (pin "16") (pinfunction "PA2_16") (pintype "bidirectional"))
      (node (ref "IC6") (pin "10") (pinfunction "IO15_10") (pintype "bidirectional"))
      (node (ref "R13") (pin "1") (pinfunction "1_1") (pintype "passive"))
    )
    (net (code "32") (name "/Wire-1") (class "Default")
      (node (ref "D5") (pin "1") (pinfunction "K_1") (pintype "bidirectional"))
      (node (ref "PT100") (pin "2") (pinfunction "2_2") (pintype "bidirectional"))
      (node (ref "R22") (pin "2") (pinfunction "2_2") (pintype "passive"))
    )
    (net (code "33") (name "/Wire-2") (class "Default")
      (node (ref "D4") (pin "1") (pinfunction "K_1") (pintype "bidirectional"))
      (node (ref "PT100") (pin "3") (pinfunction "3_3") (pintype "bidirectional"))
      (node (ref "R16") (pin "2") (pinfunction "2_2") (pintype "passive"))
    )
    (net (code "34") (name "/Wire-3") (class "Default")
      (node (ref "PT100") (pin "1") (pinfunction "1_1") (pintype "input"))
      (node (ref "R24") (pin "2") (pinfunction "2_2") (pintype "passive"))
      (node (ref "R26") (pin "2") (pinfunction "2_2") (pintype "passive"))
    )
    (net (code "35") (name "/nADS-CS") (class "Default")
      (node (ref "IC4") (pin "2") (pinfunction "!CS_2") (pintype "bidirectional"))
      (node (ref "IC5") (pin "20") (pinfunction "PA4_20") (pintype "bidirectional"))
      (node (ref "R32") (pin "1") (pinfunction "1_1") (pintype "passive"))
    )
    (net (code "36") (name "/nDAC-CS") (class "Default")
      (node (ref "IC3") (pin "6") (pinfunction "CSB_6") (pintype "bidirectional"))
      (node (ref "IC5") (pin "51") (pinfunction "PC10_51") (pintype "bidirectional"))
      (node (ref "R21") (pin "1") (pinfunction "1_1") (pintype "passive"))
    )
    (net (code "37") (name "/nDAC-ERROR") (class "Default")
      (node (ref "IC3") (pin "7") (pinfunction "ERRB_7") (pintype "bidirectional"))
      (node (ref "IC5") (pin "40") (pinfunction "PC9_40") (pintype "bidirectional"))
      (node (ref "R27") (pin "1") (pinfunction "1_1") (pintype "passive"))
    )
    (net (code "38") (name "GND") (class "Default")
      (node (ref "1") (pin "2") (pinfunction "2_2") (pintype "bidirectional"))
      (node (ref "BOOT_0") (pin "3") (pinfunction "3_3") (pintype "bidirectional"))
      (node (ref "BOOT_1") (pin "3") (pinfunction "3_3") (pintype "bidirectional"))
      (node (ref "C1") (pin "1") (pinfunction "1_1") (pintype "passive"))
      (node (ref "C10") (pin "1") (pinfunction "1_1") (pintype "passive"))
      (node (ref "C11") (pin "1") (pinfunction "1_1") (pintype "passive"))
      (node (ref "C12") (pin "1") (pinfunction "1_1") (pintype "passive"))
      (node (ref "C13") (pin "1") (pinfunction "1_1") (pintype "passive"))
      (node (ref "C14") (pin "1") (pinfunction "1_1") (pintype "passive"))
      (node (ref "C15") (pin "1") (pinfunction "1_1") (pintype "passive"))
      (node (ref "C16") (pin "1") (pinfunction "1_1") (pintype "passive"))
      (node (ref "C18") (pin "1") (pinfunction "1_1") (pintype "passive"))
      (node (ref "C19") (pin "2") (pinfunction "2_2") (pintype "passive"))
      (node (ref "C20") (pin "1") (pinfunction "1_1") (pintype "passive"))
      (node (ref "C21") (pin "1") (pinfunction "1_1") (pintype "passive"))
      (node (ref "C22") (pin "2") (pinfunction "2_2") (pintype "passive"))
      (node (ref "C23") (pin "1") (pinfunction "1_1") (pintype "passive"))
      (node (ref "C24") (pin "1") (pinfunction "1_1") (pintype "passive"))
      (node (ref "C26") (pin "1") (pinfunction "1_1") (pintype "passive"))
      (node (ref "C27") (pin "1") (pinfunction "1_1") (pintype "passive"))
      (node (ref "C28") (pin "1") (pinfunction "1_1") (pintype "passive"))
      (node (ref "C29") (pin "1") (pinfunction "1_1") (pintype "passive"))
      (node (ref "C3") (pin "1") (pinfunction "1_1") (pintype "passive"))
      (node (ref "C30") (pin "1") (pinfunction "1_1") (pintype "passive"))
      (node (ref "C31") (pin "1") (pinfunction "1_1") (pintype "passive"))
      (node (ref "C32") (pin "1") (pinfunction "1_1") (pintype "passive"))
      (node (ref "C33") (pin "1") (pinfunction "1_1") (pintype "passive"))
      (node (ref "C34") (pin "1") (pinfunction "1_1") (pintype "passive"))
      (node (ref "C36") (pin "1") (pinfunction "1_1") (pintype "passive"))
      (node (ref "C37") (pin "1") (pinfunction "1_1") (pintype "passive"))
      (node (ref "C7") (pin "1") (pinfunction "1_1") (pintype "passive"))
      (node (ref "C8") (pin "1") (pinfunction "1_1") (pintype "passive"))
      (node (ref "C9") (pin "2") (pinfunction "2_2") (pintype "passive"))
      (node (ref "ESP Flash") (pin "1") (pinfunction "1_1") (pintype "passive"))
      (node (ref "IC1") (pin "4") (pinfunction "GND_4") (pintype "power_in"))
      (node (ref "IC3") (pin "1") (pinfunction "COMA_1") (pintype "bidirectional"))
      (node (ref "IC3") (pin "11") (pinfunction "NC_11") (pintype "passive"))
      (node (ref "IC3") (pin "17") (pinfunction "GND_17") (pintype "bidirectional"))
      (node (ref "IC3") (pin "2") (pinfunction "COMD_2") (pintype "bidirectional"))
      (node (ref "IC4") (pin "4") (pinfunction "DGND_4") (pintype "bidirectional"))
      (node (ref "IC4") (pin "5") (pinfunction "AVSS_5") (pintype "bidirectional"))
      (node (ref "IC5") (pin "12") (pinfunction "VSSA_12") (pintype "bidirectional"))
      (node (ref "IC5") (pin "18") (pinfunction "VSS_4_18") (pintype "bidirectional"))
      (node (ref "IC5") (pin "31") (pinfunction "VSS_1_31") (pintype "bidirectional"))
      (node (ref "IC5") (pin "47") (pinfunction "VSS_2_47") (pintype "bidirectional"))
      (node (ref "IC5") (pin "63") (pinfunction "VSS_3_63") (pintype "bidirectional"))
      (node (ref "IC6") (pin "9") (pinfunction "GND_9") (pintype "bidirectional"))
      (node (ref "IC7") (pin "2") (pinfunction "GND_2") (pintype "power_in"))
      (node (ref "J2") (pin "1") (pinfunction "GND_1") (pintype "passive"))
      (node (ref "J2") (pin "2") (pinfunction "GND_2") (pintype "passive"))
      (node (ref "LCD") (pin "4") (pinfunction "4_4") (pintype "power_in"))
      (node (ref "Q1") (pin "3") (pinfunction "S2_3") (pintype "bidirectional"))
      (node (ref "R10") (pin "2") (pinfunction "2_2") (pintype "passive"))
      (node (ref "R13") (pin "2") (pinfunction "2_2") (pintype "passive"))
      (node (ref "R17") (pin "1") (pinfunction "1_1") (pintype "passive"))
      (node (ref "R26") (pin "1") (pinfunction "1_1") (pintype "passive"))
      (node (ref "R29") (pin "2") (pinfunction "2_2") (pintype "passive"))
      (node (ref "R3") (pin "1") (pinfunction "1_1") (pintype "passive"))
      (node (ref "R30") (pin "1") (pinfunction "1_1") (pintype "passive"))
      (node (ref "R5") (pin "1") (pinfunction "1_1") (pintype "passive"))
      (node (ref "R6") (pin "1") (pinfunction "1_1") (pintype "passive"))
      (node (ref "S2") (pin "2") (pinfunction "2_2") (pintype "bidirectional"))
      (node (ref "SWD") (pin "1") (pinfunction "1_1") (pintype "power_in"))
      (node (ref "U1") (pin "2") (pinfunction "VSS_2") (pintype "power_in"))
      (node (ref "U2") (pin "1") (pinfunction "GND_1") (pintype "power_in"))
    )
    (net (code "39") (name "Net-(BOOT_0-COM)") (class "Default")
      (node (ref "BOOT_0") (pin "2") (pinfunction "COM_2") (pintype "bidirectional"))
      (node (ref "R12") (pin "2") (pinfunction "2_2") (pintype "passive"))
    )
    (net (code "40") (name "Net-(BOOT_1-COM)") (class "Default")
      (node (ref "BOOT_1") (pin "2") (pinfunction "COM_2") (pintype "bidirectional"))
      (node (ref "R31") (pin "1") (pinfunction "1_1") (pintype "passive"))
    )
    (net (code "41") (name "Net-(C23-Pad2)") (class "Default")
      (node (ref "C23") (pin "2") (pinfunction "2_2") (pintype "passive"))
      (node (ref "R25") (pin "2") (pinfunction "2_2") (pintype "passive"))
      (node (ref "Y1") (pin "2") (pinfunction "2_2") (pintype "bidirectional"))
    )
    (net (code "42") (name "Net-(D1-K)") (class "Default")
      (node (ref "C1") (pin "2") (pinfunction "2_2") (pintype "passive"))
      (node (ref "D1") (pin "1") (pinfunction "K_1") (pintype "bidirectional"))
      (node (ref "IC1") (pin "5") (pinfunction "EN_5") (pintype "bidirectional"))
      (node (ref "IC1") (pin "8") (pinfunction "IN_8") (pintype "power_in"))
    )
    (net (code "43") (name "Net-(D2-K)") (class "Default")
      (node (ref "D2") (pin "3") (pinfunction "K_3") (pintype "passive"))
      (node (ref "U1") (pin "4") (pinfunction "VDD_4") (pintype "power_in"))
    )
    (net (code "44") (name "Net-(D3-A)") (class "Default")
      (node (ref "D3") (pin "2") (pinfunction "A_2") (pintype "bidirectional"))
      (node (ref "IC3") (pin "9") (pinfunction "OUT_9") (pintype "bidirectional"))
    )
    (net (code "45") (name "Net-(D4-A)") (class "Default")
      (node (ref "D4") (pin "2") (pinfunction "A_2") (pintype "bidirectional"))
      (node (ref "IC4") (pin "6") (pinfunction "AIN3/REFN1_6") (pintype "bidirectional"))
    )
    (net (code "46") (name "Net-(D5-A)") (class "Default")
      (node (ref "D5") (pin "2") (pinfunction "A_2") (pintype "bidirectional"))
      (node (ref "IC4") (pin "7") (pinfunction "AIN2_7") (pintype "bidirectional"))
    )
    (net (code "47") (name "Net-(D6-K)") (class "Default")
      (node (ref "C33") (pin "2") (pinfunction "2_2") (pintype "passive"))
      (node (ref "D6") (pin "1") (pinfunction "K_1") (pintype "bidirectional"))
      (node (ref "IC7") (pin "1") (pinfunction "VIN_1") (pintype "power_in"))
      (node (ref "IC7") (pin "3") (pinfunction "!SHDN_3") (pintype "bidirectional"))
      (node (ref "Q3") (pin "3") (pinfunction "D_3") (pintype "bidirectional"))
    )
    (net (code "48") (name "Net-(D7-A)") (class "Default")
      (node (ref "D7") (pin "1") (pinfunction "A_1") (pintype "passive"))
      (node (ref "R2") (pin "2") (pinfunction "2_2") (pintype "passive"))
    )
    (net (code "49") (name "Net-(D7-K)") (class "Default")
      (node (ref "D7") (pin "2") (pinfunction "K_2") (pintype "passive"))
      (node (ref "U1") (pin "1") (pinfunction "STAT_1") (pintype "input"))
    )
    (net (code "50") (name "Net-(IC1-FB)") (class "Default")
      (node (ref "C2") (pin "1") (pinfunction "1_1") (pintype "passive"))
      (node (ref "IC1") (pin "2") (pinfunction "FB_2") (pintype "bidirectional"))
      (node (ref "R1") (pin "1") (pinfunction "1_1") (pintype "passive"))
      (node (ref "R6") (pin "2") (pinfunction "2_2") (pintype "passive"))
    )
    (net (code "51") (name "Net-(IC1-NR{slash}SS)") (class "Default")
      (node (ref "C3") (pin "2") (pinfunction "2_2") (pintype "passive"))
      (node (ref "IC1") (pin "6") (pinfunction "NR/SS_6") (pintype "bidirectional"))
    )
    (net (code "52") (name "Net-(IC2-CS)") (class "Default")
      (node (ref "IC2") (pin "2") (pinfunction "CS_2") (pintype "bidirectional"))
      (node (ref "R5") (pin "2") (pinfunction "2_2") (pintype "passive"))
    )
    (net (code "53") (name "Net-(IC2-GND)") (class "Default")
      (node (ref "C4") (pin "1") (pinfunction "1_1") (pintype "passive"))
      (node (ref "IC2") (pin "6") (pinfunction "GND_6") (pintype "power_in"))
      (node (ref "Q1") (pin "1") (pinfunction "S1_1") (pintype "bidirectional"))
      (node (ref "U3") (pin "1") (pinfunction "-_1_1") (pintype "bidirectional"))
      (node (ref "U3") (pin "3") (pinfunction "-_2_3") (pintype "bidirectional"))
    )
    (net (code "54") (name "Net-(IC2-OC)") (class "Default")
      (node (ref "IC2") (pin "3") (pinfunction "OC_3") (pintype "bidirectional"))
      (node (ref "Q1") (pin "4") (pinfunction "G2_4") (pintype "bidirectional"))
    )
    (net (code "55") (name "Net-(IC2-OD)") (class "Default")
      (node (ref "IC2") (pin "1") (pinfunction "OD_1") (pintype "bidirectional"))
      (node (ref "Q1") (pin "6") (pinfunction "G1_6") (pintype "bidirectional"))
    )
    (net (code "56") (name "Net-(IC2-VCC)") (class "Default")
      (node (ref "C4") (pin "2") (pinfunction "2_2") (pintype "passive"))
      (node (ref "IC2") (pin "5") (pinfunction "VCC_5") (pintype "power_in"))
      (node (ref "R4") (pin "2") (pinfunction "2_2") (pintype "passive"))
    )
    (net (code "57") (name "Net-(IC3-BASE)") (class "Default")
      (node (ref "IC3") (pin "16") (pinfunction "BASE_16") (pintype "bidirectional"))
      (node (ref "Q2") (pin "1") (pinfunction "B_1") (pintype "bidirectional"))
    )
    (net (code "58") (name "Net-(IC3-C1)") (class "Default")
      (node (ref "C11") (pin "2") (pinfunction "2_2") (pintype "passive"))
      (node (ref "IC3") (pin "14") (pinfunction "C1_14") (pintype "bidirectional"))
    )
    (net (code "59") (name "Net-(IC3-C2)") (class "Default")
      (node (ref "C7") (pin "2") (pinfunction "2_2") (pintype "passive"))
      (node (ref "C8") (pin "2") (pinfunction "2_2") (pintype "passive"))
      (node (ref "IC3") (pin "13") (pinfunction "C2_13") (pintype "bidirectional"))
    )
    (net (code "60") (name "Net-(IC3-C3)") (class "Default")
      (node (ref "C9") (pin "1") (pinfunction "1_1") (pintype "passive"))
      (node (ref "IC3") (pin "12") (pinfunction "C3_12") (pintype "bidirectional"))
    )
    (net (code "61") (name "Net-(IC4-CLK)") (class "Default")
      (node (ref "IC4") (pin "3") (pinfunction "CLK_3") (pintype "bidirectional"))
      (node (ref "R17") (pin "2") (pinfunction "2_2") (pintype "passive"))
    )
    (net (code "62") (name "Net-(IC5-BOOT0)") (class "Default")
      (node (ref "IC5") (pin "60") (pinfunction "BOOT0_60") (pintype "bidirectional"))
      (node (ref "R12") (pin "1") (pinfunction "1_1") (pintype "passive"))
    )
    (net (code "63") (name "Net-(IC5-OSC_IN)") (class "Default")
      (node (ref "C22") (pin "1") (pinfunction "1_1") (pintype "passive"))
      (node (ref "IC5") (pin "5") (pinfunction "OSC_IN_5") (pintype "bidirectional"))
      (node (ref "Y1") (pin "1") (pinfunction "1_1") (pintype "bidirectional"))
    )
    (net (code "64") (name "Net-(IC5-OSC_OUT)") (class "Default")
      (node (ref "IC5") (pin "6") (pinfunction "OSC_OUT_6") (pintype "bidirectional"))
      (node (ref "R25") (pin "1") (pinfunction "1_1") (pintype "passive"))
    )
    (net (code "65") (name "Net-(IC5-PB2)") (class "Default")
      (node (ref "IC5") (pin "28") (pinfunction "PB2_28") (pintype "bidirectional"))
      (node (ref "R31") (pin "2") (pinfunction "2_2") (pintype "passive"))
    )
    (net (code "66") (name "Net-(IC6-EN)") (class "Default")
      (node (ref "IC6") (pin "3") (pinfunction "EN_3") (pintype "bidirectional"))
      (node (ref "R8") (pin "2") (pinfunction "2_2") (pintype "passive"))
    )
    (net (code "67") (name "Net-(IC6-IO2)") (class "Default")
      (node (ref "IC6") (pin "11") (pinfunction "IO2_11") (pintype "bidirectional"))
      (node (ref "R11") (pin "2") (pinfunction "2_2") (pintype "passive"))
    )
    (net (code "68") (name "Net-(IC7-LX)") (class "Default")
      (node (ref "IC7") (pin "5") (pinfunction "LX_5") (pintype "bidirectional"))
      (node (ref "L1") (pin "2") (pinfunction "2_2") (pintype "passive"))
    )
    (net (code "69") (name "Net-(J2-SIG)") (class "Default")
      (node (ref "J2") (pin "3") (pinfunction "SIG_3") (pintype "passive"))
      (node (ref "U2") (pin "9") (pinfunction "ANT_9") (pintype "passive"))
    )
    (net (code "70") (name "Net-(Q2-E)") (class "Default")
      (node (ref "Q2") (pin "2") (pinfunction "E_2") (pintype "bidirectional"))
      (node (ref "R10") (pin "1") (pinfunction "1_1") (pintype "passive"))
    )
    (net (code "71") (name "Net-(U1-PROG)") (class "Default")
      (node (ref "R3") (pin "2") (pinfunction "2_2") (pintype "passive"))
      (node (ref "U1") (pin "5") (pinfunction "PROG_5") (pintype "input"))
    )
    (net (code "72") (name "VCC") (class "Default")
      (node (ref "C10") (pin "2") (pinfunction "2_2") (pintype "passive"))
      (node (ref "C12") (pin "2") (pinfunction "2_2") (pintype "passive"))
      (node (ref "C13") (pin "2") (pinfunction "2_2") (pintype "passive"))
      (node (ref "C2") (pin "2") (pinfunction "2_2") (pintype "passive"))
      (node (ref "IC1") (pin "1") (pinfunction "OUT_1") (pintype "power_in"))
      (node (ref "IC3") (pin "15") (pinfunction "VA_15") (pintype "bidirectional"))
      (node (ref "IC3") (pin "3") (pinfunction "VD_3") (pintype "bidirectional"))
      (node (ref "R1") (pin "2") (pinfunction "2_2") (pintype "passive"))
    )
    (net (code "73") (name "Vbat") (class "Default")
      (node (ref "Q3") (pin "2") (pinfunction "S_2") (pintype "bidirectional"))
      (node (ref "R4") (pin "1") (pinfunction "1_1") (pintype "passive"))
      (node (ref "U1") (pin "3") (pinfunction "VBAT_3") (pintype "power_in"))
      (node (ref "U3") (pin "2") (pinfunction "+_1_2") (pintype "bidirectional"))
      (node (ref "U3") (pin "4") (pinfunction "+_2_4") (pintype "bidirectional"))
    )
    (net (code "74") (name "unconnected-(IC1-DNC-Pad7)") (class "Default")
      (node (ref "IC1") (pin "7") (pinfunction "DNC_7") (pintype "bidirectional+no_connect"))
    )
    (net (code "75") (name "unconnected-(IC1-EP-Pad9)") (class "Default")
      (node (ref "IC1") (pin "9") (pinfunction "EP_9") (pintype "power_in+no_connect"))
    )
    (net (code "76") (name "unconnected-(IC1-NC-Pad3)") (class "Default")
      (node (ref "IC1") (pin "3") (pinfunction "NC_3") (pintype "passive+no_connect"))
    )
    (net (code "77") (name "unconnected-(IC2-TD-Pad4)") (class "Default")
      (node (ref "IC2") (pin "4") (pinfunction "TD_4") (pintype "bidirectional"))
    )
    (net (code "78") (name "unconnected-(IC5-PA0-WKUP-Pad14)") (class "Default")
      (node (ref "IC5") (pin "14") (pinfunction "PA0-WKUP_14") (pintype "bidirectional"))
    )
    (net (code "79") (name "unconnected-(IC5-PA1-Pad15)") (class "Default")
      (node (ref "IC5") (pin "15") (pinfunction "PA1_15") (pintype "bidirectional"))
    )
    (net (code "80") (name "unconnected-(IC5-PA8-Pad41)") (class "Default")
      (node (ref "IC5") (pin "41") (pinfunction "PA8_41") (pintype "bidirectional"))
    )
    (net (code "81") (name "unconnected-(IC5-PA11-Pad44)") (class "Default")
      (node (ref "IC5") (pin "44") (pinfunction "PA11_44") (pintype "bidirectional"))
    )
    (net (code "82") (name "unconnected-(IC5-PA12-Pad45)") (class "Default")
      (node (ref "IC5") (pin "45") (pinfunction "PA12_45") (pintype "bidirectional"))
    )
    (net (code "83") (name "unconnected-(IC5-PB0-Pad26)") (class "Default")
      (node (ref "IC5") (pin "26") (pinfunction "PB0_26") (pintype "bidirectional"))
    )
    (net (code "84") (name "unconnected-(IC5-PB1-Pad27)") (class "Default")
      (node (ref "IC5") (pin "27") (pinfunction "PB1_27") (pintype "bidirectional"))
    )
    (net (code "85") (name "unconnected-(IC5-PB4-Pad56)") (class "Default")
      (node (ref "IC5") (pin "56") (pinfunction "PB4_56") (pintype "bidirectional"))
    )
    (net (code "86") (name "unconnected-(IC5-PB5-Pad57)") (class "Default")
      (node (ref "IC5") (pin "57") (pinfunction "PB5_57") (pintype "bidirectional"))
    )
    (net (code "87") (name "unconnected-(IC5-PB8-Pad61)") (class "Default")
      (node (ref "IC5") (pin "61") (pinfunction "PB8_61") (pintype "bidirectional"))
    )
    (net (code "88") (name "unconnected-(IC5-PB9-Pad62)") (class "Default")
      (node (ref "IC5") (pin "62") (pinfunction "PB9_62") (pintype "bidirectional"))
    )
    (net (code "89") (name "unconnected-(IC5-PB10-Pad29)") (class "Default")
      (node (ref "IC5") (pin "29") (pinfunction "PB10_29") (pintype "bidirectional"))
    )
    (net (code "90") (name "unconnected-(IC5-PB11-Pad30)") (class "Default")
      (node (ref "IC5") (pin "30") (pinfunction "PB11_30") (pintype "bidirectional"))
    )
    (net (code "91") (name "unconnected-(IC5-PC0-Pad8)") (class "Default")
      (node (ref "IC5") (pin "8") (pinfunction "PC0_8") (pintype "bidirectional"))
    )
    (net (code "92") (name "unconnected-(IC5-PC1-Pad9)") (class "Default")
      (node (ref "IC5") (pin "9") (pinfunction "PC1_9") (pintype "bidirectional"))
    )
    (net (code "93") (name "unconnected-(IC5-PC2-Pad10)") (class "Default")
      (node (ref "IC5") (pin "10") (pinfunction "PC2_10") (pintype "bidirectional"))
    )
    (net (code "94") (name "unconnected-(IC5-PC3-Pad11)") (class "Default")
      (node (ref "IC5") (pin "11") (pinfunction "PC3_11") (pintype "bidirectional"))
    )
    (net (code "95") (name "unconnected-(IC5-PC4-Pad24)") (class "Default")
      (node (ref "IC5") (pin "24") (pinfunction "PC4_24") (pintype "bidirectional"))
    )
    (net (code "96") (name "unconnected-(IC5-PC5-Pad25)") (class "Default")
      (node (ref "IC5") (pin "25") (pinfunction "PC5_25") (pintype "bidirectional"))
    )
    (net (code "97") (name "unconnected-(IC5-PC6-Pad37)") (class "Default")
      (node (ref "IC5") (pin "37") (pinfunction "PC6_37") (pintype "bidirectional"))
    )
    (net (code "98") (name "unconnected-(IC5-PC11-Pad52)") (class "Default")
      (node (ref "IC5") (pin "52") (pinfunction "PC11_52") (pintype "bidirectional"))
    )
    (net (code "99") (name "unconnected-(IC5-PC13-TAMPER-RTC-Pad2)") (class "Default")
      (node (ref "IC5") (pin "2") (pinfunction "PC13-TAMPER-RTC_2") (pintype "bidirectional"))
    )
    (net (code "100") (name "unconnected-(IC5-PC14-OSC32_IN-Pad3)") (class "Default")
      (node (ref "IC5") (pin "3") (pinfunction "PC14-OSC32_IN_3") (pintype "bidirectional"))
    )
    (net (code "101") (name "unconnected-(IC5-PC15-_OSC32_OUT-Pad4)") (class "Default")
      (node (ref "IC5") (pin "4") (pinfunction "PC15-_OSC32_OUT_4") (pintype "bidirectional"))
    )
    (net (code "102") (name "unconnected-(IC5-PD2-Pad54)") (class "Default")
      (node (ref "IC5") (pin "54") (pinfunction "PD2_54") (pintype "bidirectional"))
    )
    (net (code "103") (name "unconnected-(IC6-ADC-Pad2)") (class "Default")
      (node (ref "IC6") (pin "2") (pinfunction "ADC_2") (pintype "bidirectional"))
    )
    (net (code "104") (name "unconnected-(IC6-IO4-Pad13)") (class "Default")
      (node (ref "IC6") (pin "13") (pinfunction "IO4_13") (pintype "bidirectional"))
    )
    (net (code "105") (name "unconnected-(IC6-IO5-Pad14)") (class "Default")
      (node (ref "IC6") (pin "14") (pinfunction "IO5_14") (pintype "bidirectional"))
    )
    (net (code "106") (name "unconnected-(IC6-IO12-Pad6)") (class "Default")
      (node (ref "IC6") (pin "6") (pinfunction "IO12_6") (pintype "bidirectional"))
    )
    (net (code "107") (name "unconnected-(IC6-IO14-Pad5)") (class "Default")
      (node (ref "IC6") (pin "5") (pinfunction "IO14_5") (pintype "bidirectional"))
    )
    (net (code "108") (name "unconnected-(IC6-IO16-Pad4)") (class "Default")
      (node (ref "IC6") (pin "4") (pinfunction "IO16_4") (pintype "bidirectional"))
    )
    (net (code "109") (name "unconnected-(PT100-Pad4)") (class "Default")
      (node (ref "PT100") (pin "4") (pinfunction "4_4") (pintype "bidirectional+no_connect"))
    )
    (net (code "110") (name "unconnected-(Q1-1{slash}D2-Pad2)") (class "Default")
      (node (ref "Q1") (pin "2") (pinfunction "1/D2_2") (pintype "bidirectional+no_connect"))
    )
    (net (code "111") (name "unconnected-(Q1-D1{slash}D2-Pad5)") (class "Default")
      (node (ref "Q1") (pin "5") (pinfunction "D1/D2_5") (pintype "bidirectional+no_connect"))
    )
    (net (code "112") (name "unconnected-(S2-Pad3)") (class "Default")
      (node (ref "S2") (pin "3") (pinfunction "3_3") (pintype "bidirectional+no_connect"))
    )
    (net (code "113") (name "unconnected-(S2-Pad4)") (class "Default")
      (node (ref "S2") (pin "4") (pinfunction "4_4") (pintype "bidirectional+no_connect"))
    )
    (net (code "114") (name "unconnected-(SWD-Pad2)") (class "Default")
      (node (ref "SWD") (pin "2") (pinfunction "2_2") (pintype "passive+no_connect"))
    )
    (net (code "115") (name "unconnected-(U2-DIO0-Pad14)") (class "Default")
      (node (ref "U2") (pin "14") (pinfunction "DIO0_14") (pintype "bidirectional"))
    )
    (net (code "116") (name "unconnected-(U2-DIO1-Pad15)") (class "Default")
      (node (ref "U2") (pin "15") (pinfunction "DIO1_15") (pintype "bidirectional"))
    )
    (net (code "117") (name "unconnected-(U2-DIO2-Pad16)") (class "Default")
      (node (ref "U2") (pin "16") (pinfunction "DIO2_16") (pintype "bidirectional"))
    )
    (net (code "118") (name "unconnected-(U2-DIO3-Pad11)") (class "Default")
      (node (ref "U2") (pin "11") (pinfunction "DIO3_11") (pintype "bidirectional"))
    )
    (net (code "119") (name "unconnected-(U2-DIO4-Pad12)") (class "Default")
      (node (ref "U2") (pin "12") (pinfunction "DIO4_12") (pintype "bidirectional"))
    )
    (net (code "120") (name "unconnected-(U2-GND@1-Pad8)") (class "Default")
      (node (ref "U2") (pin "8") (pinfunction "GND@1_8") (pintype "power_in"))
    )
    (net (code "121") (name "unconnected-(U2-GND@2-Pad10)") (class "Default")
      (node (ref "U2") (pin "10") (pinfunction "GND@2_10") (pintype "power_in"))
    )
    (net (code "122") (name "unconnected-(U2-RESET-Pad6)") (class "Default")
      (node (ref "U2") (pin "6") (pinfunction "RESET_6") (pintype "bidirectional"))
    )
  )
)
